# OBUF.net
KiCad netlist of a schematic drawn in EAGLE
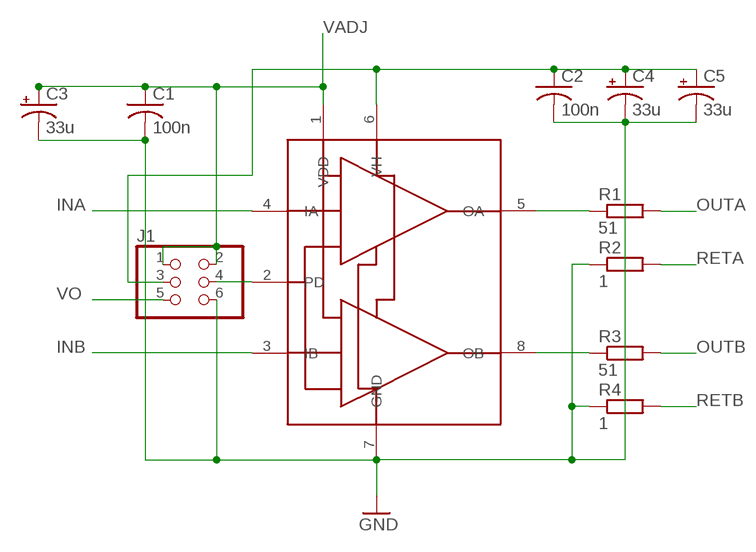
[diagram p0: schematic, sheet 1]

(export (version "E")
  (design (tool "Eeschema 10.0.6"))
  (components
    (comp (ref "C1")
      (value "100n")
      (footprint "eagle-import:C2012")
      (libsource (lib "eagle-import") (part "C-USC2012"))
    )
    (comp (ref "C2")
      (value "100n")
      (footprint "eagle-import:C2012")
      (libsource (lib "eagle-import") (part "C-USC2012"))
    )
    (comp (ref "C3")
      (value "33u")
      (footprint "eagle-import:B_3528-21R")
      (libsource (lib "eagle-import") (part "CPOL-USB/3528-21R"))
    )
    (comp (ref "C4")
      (value "33u")
      (footprint "eagle-import:B_3528-21R")
      (libsource (lib "eagle-import") (part "CPOL-USB/3528-21R"))
    )
    (comp (ref "C5")
      (value "33u")
      (footprint "eagle-import:B_3528-21R")
      (libsource (lib "eagle-import") (part "CPOL-USB/3528-21R"))
    )
    (comp (ref "J1")
      (value "PINHD-2X3")
      (footprint "eagle-import:2X03")
      (libsource (lib "eagle-import") (part "PINHD-2X3"))
    )
    (comp (ref "R1")
      (value "51")
      (footprint "eagle-import:R0805")
      (libsource (lib "eagle-import") (part "R-EU_R0805"))
    )
    (comp (ref "R2")
      (value "1")
      (footprint "eagle-import:R0805")
      (libsource (lib "eagle-import") (part "R-EU_R0805"))
    )
    (comp (ref "R3")
      (value "51")
      (footprint "eagle-import:R0805")
      (libsource (lib "eagle-import") (part "R-EU_R0805"))
    )
    (comp (ref "R4")
      (value "1")
      (footprint "eagle-import:R0805")
      (libsource (lib "eagle-import") (part "R-EU_R0805"))
    )
    (comp (ref "U$1")
      (value "ISL55110")
      (footprint "eagle-import:TSSOP8")
      (libsource (lib "eagle-import") (part "ISL55110"))
    )
  )
  (nets
    (net (code "1") (name "/INA") (class "Default")
      (node (ref "U$1") (pin "4") (pinfunction "IA_4") (pintype "input"))
    )
    (net (code "2") (name "/INB") (class "Default")
      (node (ref "U$1") (pin "3") (pinfunction "IB_3") (pintype "input"))
    )
    (net (code "3") (name "/OUTA") (class "Default")
      (node (ref "R1") (pin "2") (pinfunction "2_2") (pintype "passive"))
    )
    (net (code "4") (name "/OUTB") (class "Default")
      (node (ref "R3") (pin "2") (pinfunction "2_2") (pintype "passive"))
    )
    (net (code "5") (name "/RETA") (class "Default")
      (node (ref "R2") (pin "2") (pinfunction "2_2") (pintype "passive"))
    )
    (net (code "6") (name "/RETB") (class "Default")
      (node (ref "R4") (pin "2") (pinfunction "2_2") (pintype "passive"))
    )
    (net (code "7") (name "/VADJ") (class "Default")
      (node (ref "C1") (pin "1") (pinfunction "1_1") (pintype "passive"))
      (node (ref "C3") (pin "+") (pinfunction "+_+") (pintype "passive"))
      (node (ref "J1") (pin "1") (pinfunction "1_1") (pintype "passive"))
      (node (ref "J1") (pin "2") (pinfunction "2_2") (pintype "passive"))
      (node (ref "U$1") (pin "1") (pinfunction "VDD_1") (pintype "power_in"))
    )
    (net (code "8") (name "/VO") (class "Default")
      (node (ref "J1") (pin "5") (pinfunction "5_5") (pintype "passive"))
    )
    (net (code "9") (name "GND") (class "Default")
      (node (ref "C1") (pin "2") (pinfunction "2_2") (pintype "passive"))
      (node (ref "C2") (pin "2") (pinfunction "2_2") (pintype "passive"))
      (node (ref "C3") (pin "-") (pinfunction "-_-") (pintype "passive"))
      (node (ref "C4") (pin "-") (pinfunction "-_-") (pintype "passive"))
      (node (ref "C5") (pin "-") (pinfunction "-_-") (pintype "passive"))
      (node (ref "J1") (pin "6") (pinfunction "6_6") (pintype "passive"))
      (node (ref "R2") (pin "1") (pinfunction "1_1") (pintype "passive"))
      (node (ref "R4") (pin "1") (pinfunction "1_1") (pintype "passive"))
      (node (ref "U$1") (pin "7") (pinfunction "GND_7") (pintype "power_in"))
    )
    (net (code "10") (name "Net-(U$1-OA)") (class "Default")
      (node (ref "R1") (pin "1") (pinfunction "1_1") (pintype "passive"))
      (node (ref "U$1") (pin "5") (pinfunction "OA_5") (pintype "output"))
    )
    (net (code "11") (name "Net-(U$1-OB)") (class "Default")
      (node (ref "R3") (pin "1") (pinfunction "1_1") (pintype "passive"))
      (node (ref "U$1") (pin "8") (pinfunction "OB_8") (pintype "output"))
    )
    (net (code "12") (name "Net-(U$1-PD)") (class "Default")
      (node (ref "J1") (pin "4") (pinfunction "4_4") (pintype "passive"))
      (node (ref "U$1") (pin "2") (pinfunction "PD_2") (pintype "input"))
    )
    (net (code "13") (name "Net-(U$1-VH)") (class "Default")
      (node (ref "C2") (pin "1") (pinfunction "1_1") (pintype "passive"))
      (node (ref "C4") (pin "+") (pinfunction "+_+") (pintype "passive"))
      (node (ref "C5") (pin "+") (pinfunction "+_+") (pintype "passive"))
      (node (ref "J1") (pin "3") (pinfunction "3_3") (pintype "passive"))
      (node (ref "U$1") (pin "6") (pinfunction "VH_6") (pintype "power_in"))
    )
  )
)
